# LoadCellAmp1.net
KiCad netlist of a schematic drawn in Altium Designer
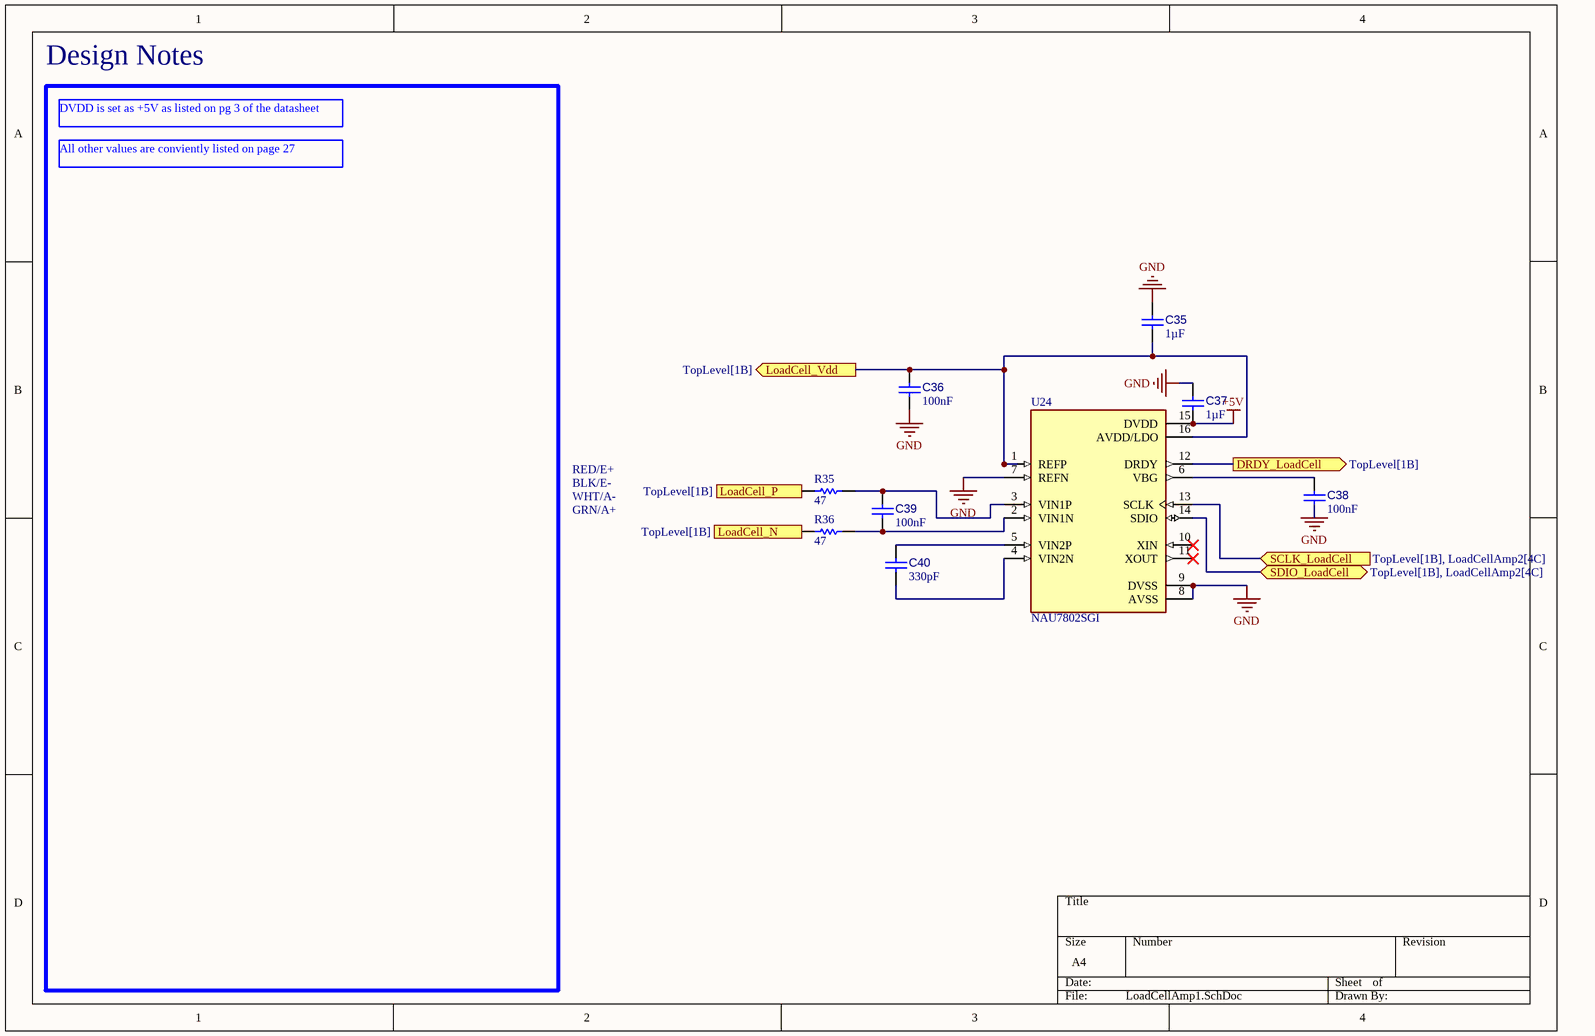
[diagram p0: LoadCellAmp1.SchDoc]

(export (version "E")
  (design (tool "Eeschema 10.0.6"))
  (components
    (comp (ref "C35")
      (value "1µF")
      (footprint "CAPC2013X135X45ML10T25")
      (description "Chip Capacitor, 1 uF, +/- 10%, 50 V, 0805 (2012 Metric)")
      (fields (field (name "TOLERANCE") "10%") (field (name "Comment") "Capacitor 1 uF +/- 10% 50 V 0805"))
      (libsource (lib "University of Calgary - SOAR") (part "CAP-NP-2"))
    )
    (comp (ref "C36")
      (value "100nF")
      (footprint "CAPC1608X90X40NL10T20")
      (description "Chip Capacitor, 100 nF, +/- 10%, 50 V, 0603 (1608 Metric)")
      (fields (field (name "TOLERANCE") "10%") (field (name "Comment") "Capacitor 100 nF +/-10% 50 V 0603"))
      (libsource (lib "University of Calgary - SOAR") (part "CAP-NP-2"))
    )
    (comp (ref "C37")
      (value "1µF")
      (footprint "CAPC2013X135X45ML10T25")
      (description "Chip Capacitor, 1 uF, +/- 10%, 50 V, 0805 (2012 Metric)")
      (fields (field (name "TOLERANCE") "10%") (field (name "Comment") "Capacitor 1 uF +/- 10% 50 V 0805"))
      (libsource (lib "University of Calgary - SOAR") (part "CAP-NP-2"))
    )
    (comp (ref "C38")
      (value "100nF")
      (footprint "CAPC1608X90X40NL10T20")
      (description "Chip Capacitor, 100 nF, +/- 10%, 50 V, 0603 (1608 Metric)")
      (fields (field (name "TOLERANCE") "10%") (field (name "Comment") "Capacitor 100 nF +/-10% 50 V 0603"))
      (libsource (lib "University of Calgary - SOAR") (part "CAP-NP-2"))
    )
    (comp (ref "C39")
      (value "100nF")
      (footprint "CAPC1608X90X40NL10T20")
      (description "Chip Capacitor, 100 nF, +/- 10%, 50 V, 0603 (1608 Metric)")
      (fields (field (name "TOLERANCE") "10%") (field (name "Comment") "Capacitor 100 nF +/-10% 50 V 0603"))
      (libsource (lib "University of Calgary - SOAR") (part "CAP-NP-2"))
    )
    (comp (ref "C40")
      (value "330pF")
      (footprint "CAP_0603")
      (description "KGM15ACG1H331FT - Cap Ceramic 330pF 50V C0G 1% Pad SMD 0603 125C T/R")
      (fields (field (name "Comment") "CAP CER 330pF 50V 1% 0603"))
      (libsource (lib "University of Calgary - SOAR") (part "CAP-NP-2"))
    )
    (comp (ref "R35")
      (value "47")
      (footprint "RESC1608X50X30ML20T20")
      (description "Fixed Resistor, Metal Film, 0.1W, 47ohm, 75V, 0.05% +/-Tol, 10ppm/Cel, Surface Mount, 0603")
      (fields (field (name "TOLERANCE") "0.05%") (field (name "POWER") "100mW"))
      (libsource (lib "University of Calgary - SOAR") (part "RES"))
    )
    (comp (ref "R36")
      (value "47")
      (footprint "RESC1608X50X30ML20T20")
      (description "Fixed Resistor, Metal Film, 0.1W, 47ohm, 75V, 0.05% +/-Tol, 10ppm/Cel, Surface Mount, 0603")
      (fields (field (name "TOLERANCE") "0.05%") (field (name "POWER") "100mW"))
      (libsource (lib "University of Calgary - SOAR") (part "RES"))
    )
    (comp (ref "U24")
      (value "NAU7802SGI")
      (footprint "NAU7802SGI-Footprint-1")
      (description "ADC, Delta-Sigma, 24-Bit, 1 Func, 2 Channel, Serial Access, PDSO16")
      (libsource (lib "University of Calgary - SOAR") (part "AMP-3"))
    )
  )
  (nets
    (net (code "1") (name "+5V") (class "Default")
      (node (ref "C37") (pin "1") (pinfunction "1_1") (pintype "passive"))
      (node (ref "U24") (pin "15") (pinfunction "DVDD_15") (pintype "power_in"))
    )
    (net (code "2") (name "/DRDY_LoadCell") (class "Default")
      (node (ref "U24") (pin "12") (pinfunction "DRDY_12") (pintype "output"))
    )
    (net (code "3") (name "/LoadCell_N") (class "Default")
      (node (ref "R36") (pin "1") (pinfunction "1_1") (pintype "passive"))
    )
    (net (code "4") (name "/LoadCell_P") (class "Default")
      (node (ref "R35") (pin "1") (pinfunction "1_1") (pintype "passive"))
    )
    (net (code "5") (name "/LoadCell_Vdd") (class "Default")
      (node (ref "C35") (pin "1") (pinfunction "1_1") (pintype "passive"))
      (node (ref "C36") (pin "2") (pinfunction "2_2") (pintype "passive"))
      (node (ref "U24") (pin "1") (pinfunction "REFP_1") (pintype "input"))
      (node (ref "U24") (pin "16") (pinfunction "AVDD/LDO_16") (pintype "power_in"))
    )
    (net (code "6") (name "/SCLK_LoadCell") (class "Default")
      (node (ref "U24") (pin "13") (pinfunction "SCLK_13") (pintype "input"))
    )
    (net (code "7") (name "/SDIO_LoadCell") (class "Default")
      (node (ref "U24") (pin "14") (pinfunction "SDIO_14") (pintype "bidirectional"))
    )
    (net (code "8") (name "GND") (class "Default")
      (node (ref "C35") (pin "2") (pinfunction "2_2") (pintype "passive"))
      (node (ref "C36") (pin "1") (pinfunction "1_1") (pintype "passive"))
      (node (ref "C37") (pin "2") (pinfunction "2_2") (pintype "passive"))
      (node (ref "C38") (pin "1") (pinfunction "1_1") (pintype "passive"))
      (node (ref "U24") (pin "7") (pinfunction "REFN_7") (pintype "input"))
      (node (ref "U24") (pin "8") (pinfunction "AVSS_8") (pintype "power_in"))
      (node (ref "U24") (pin "9") (pinfunction "DVSS_9") (pintype "power_in"))
    )
    (net (code "9") (name "Net-(U24-VBG)") (class "Default")
      (node (ref "C38") (pin "2") (pinfunction "2_2") (pintype "passive"))
      (node (ref "U24") (pin "6") (pinfunction "VBG_6") (pintype "output"))
    )
    (net (code "10") (name "Net-(U24-VIN1N)") (class "Default")
      (node (ref "C39") (pin "1") (pinfunction "1_1") (pintype "passive"))
      (node (ref "R36") (pin "2") (pinfunction "2_2") (pintype "passive"))
      (node (ref "U24") (pin "2") (pinfunction "VIN1N_2") (pintype "input"))
    )
    (net (code "11") (name "Net-(U24-VIN1P)") (class "Default")
      (node (ref "C39") (pin "2") (pinfunction "2_2") (pintype "passive"))
      (node (ref "R35") (pin "2") (pinfunction "2_2") (pintype "passive"))
      (node (ref "U24") (pin "3") (pinfunction "VIN1P_3") (pintype "input"))
    )
    (net (code "12") (name "Net-(U24-VIN2N)") (class "Default")
      (node (ref "C40") (pin "1") (pinfunction "1_1") (pintype "passive"))
      (node (ref "U24") (pin "4") (pinfunction "VIN2N_4") (pintype "input"))
    )
    (net (code "13") (name "Net-(U24-VIN2P)") (class "Default")
      (node (ref "C40") (pin "2") (pinfunction "2_2") (pintype "passive"))
      (node (ref "U24") (pin "5") (pinfunction "VIN2P_5") (pintype "input"))
    )
    (net (code "14") (name "unconnected-(U24-XIN-Pad10)") (class "Default")
      (node (ref "U24") (pin "10") (pinfunction "XIN_10") (pintype "input+no_connect"))
    )
    (net (code "15") (name "unconnected-(U24-XOUT-Pad11)") (class "Default")
      (node (ref "U24") (pin "11") (pinfunction "XOUT_11") (pintype "output+no_connect"))
    )
  )
)
